# AnalogOutput.net
KiCad netlist of a schematic drawn in Altium Designer
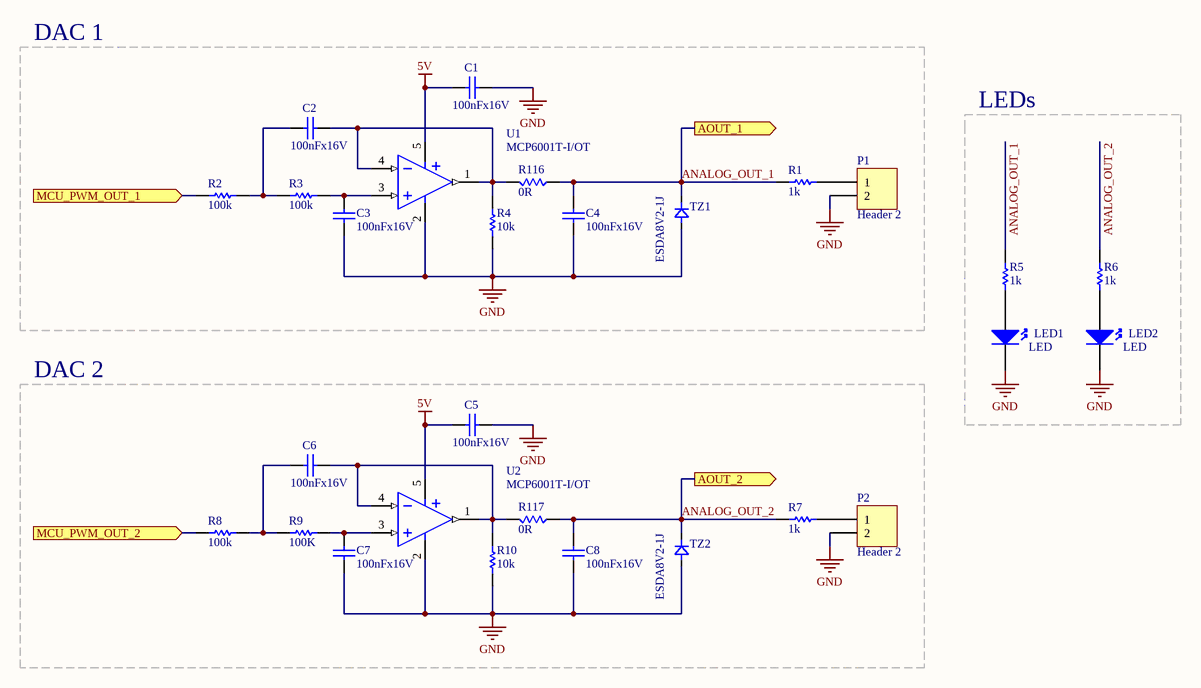
[diagram p0: AnalogOutput.SchDoc]

(export (version "E")
  (design (tool "Eeschema 10.0.6"))
  (components
    (comp (ref "C1")
      (value "100nFx16V")
      (footprint "DISC-0805")
      (description "Capacitor")
      (libsource (lib "IntLib") (part "Cap"))
    )
    (comp (ref "C2")
      (value "100nFx16V")
      (footprint "DISC-0805")
      (description "Capacitor")
      (libsource (lib "IntLib") (part "Cap"))
    )
    (comp (ref "C3")
      (value "100nFx16V")
      (footprint "DISC-0805")
      (description "Capacitor")
      (libsource (lib "IntLib") (part "Cap"))
    )
    (comp (ref "C4")
      (value "100nFx16V")
      (footprint "DISC-0805")
      (description "Capacitor")
      (libsource (lib "IntLib") (part "Cap"))
    )
    (comp (ref "C5")
      (value "100nFx16V")
      (footprint "DISC-0805")
      (description "Capacitor")
      (libsource (lib "IntLib") (part "Cap"))
    )
    (comp (ref "C6")
      (value "100nFx16V")
      (footprint "DISC-0805")
      (description "Capacitor")
      (libsource (lib "IntLib") (part "Cap"))
    )
    (comp (ref "C7")
      (value "100nFx16V")
      (footprint "DISC-0805")
      (description "Capacitor")
      (libsource (lib "IntLib") (part "Cap"))
    )
    (comp (ref "C8")
      (value "100nFx16V")
      (footprint "DISC-0805")
      (description "Capacitor")
      (libsource (lib "IntLib") (part "Cap"))
    )
    (comp (ref "LED1") (value "LED") (footprint "DISC-LED-0.1-PTH") (libsource (lib "IntLib") (part "LED")))
    (comp (ref "LED2") (value "LED") (footprint "DISC-LED-0.1-PTH") (libsource (lib "IntLib") (part "LED")))
    (comp (ref "P1")
      (value "Header 2")
      (footprint "CON-FLEXWIRE-0.5MM2-1X2")
      (description "Header, 2-Pin")
      (fields (field (name "PUBLISHER") "Altium Limited"))
      (libsource (lib "IntLib") (part "Header 2"))
    )
    (comp (ref "P2")
      (value "Header 2")
      (footprint "CON-FLEXWIRE-0.5MM2-1X2")
      (description "Header, 2-Pin")
      (fields (field (name "PUBLISHER") "Altium Limited"))
      (libsource (lib "IntLib") (part "Header 2"))
    )
    (comp (ref "R1")
      (value "1k")
      (footprint "DISC-0805")
      (description "Resistor")
      (libsource (lib "IntLib") (part "Res"))
    )
    (comp (ref "R2")
      (value "100k")
      (footprint "DISC-0805")
      (description "Resistor")
      (libsource (lib "IntLib") (part "Res"))
    )
    (comp (ref "R3")
      (value "100k")
      (footprint "DISC-0805")
      (description "Resistor")
      (libsource (lib "IntLib") (part "Res"))
    )
    (comp (ref "R4")
      (value "10k")
      (footprint "DISC-0805")
      (description "Resistor")
      (libsource (lib "IntLib") (part "Res"))
    )
    (comp (ref "R5")
      (value "1k")
      (footprint "DISC-0805")
      (description "Resistor")
      (libsource (lib "IntLib") (part "Res"))
    )
    (comp (ref "R6")
      (value "1k")
      (footprint "DISC-0805")
      (description "Resistor")
      (libsource (lib "IntLib") (part "Res"))
    )
    (comp (ref "R7")
      (value "1k")
      (footprint "DISC-0805")
      (description "Resistor")
      (libsource (lib "IntLib") (part "Res"))
    )
    (comp (ref "R8")
      (value "100k")
      (footprint "DISC-0805")
      (description "Resistor")
      (libsource (lib "IntLib") (part "Res"))
    )
    (comp (ref "R9")
      (value "100K")
      (footprint "DISC-0805")
      (description "Resistor")
      (libsource (lib "IntLib") (part "Res"))
    )
    (comp (ref "R10")
      (value "10k")
      (footprint "DISC-0805")
      (description "Resistor")
      (libsource (lib "IntLib") (part "Res"))
    )
    (comp (ref "R116")
      (value "0R")
      (footprint "DISC-0805")
      (description "Resistor")
      (libsource (lib "AUTOTRAC") (part "RESISTOR"))
    )
    (comp (ref "R117")
      (value "0R")
      (footprint "DISC-0805")
      (description "Resistor")
      (libsource (lib "AUTOTRAC") (part "RESISTOR"))
    )
    (comp (ref "TZ1")
      (value "ESDA8V2-1J")
      (footprint "DISC-SOD-323")
      (description "TVZ-Unidirectional")
      (libsource (lib "IntLib") (part "TVZ-Unidirectional"))
    )
    (comp (ref "TZ2")
      (value "ESDA8V2-1J")
      (footprint "DISC-SOD-323")
      (description "TVZ-Unidirectional")
      (libsource (lib "IntLib") (part "TVZ-Unidirectional"))
    )
    (comp (ref "U1")
      (value "MCP6001T-I/OT")
      (footprint "CI-SOT-23-5")
      (description "Operational Amplifiers - Op Amps Single 1.8V 1MHz")
      (libsource (lib "IntLib") (part "MCP6001T-I/OT"))
    )
    (comp (ref "U2")
      (value "MCP6001T-I/OT")
      (footprint "CI-SOT-23-5")
      (description "Operational Amplifiers - Op Amps Single 1.8V 1MHz")
      (libsource (lib "IntLib") (part "MCP6001T-I/OT"))
    )
  )
  (nets
    (net (code "1") (name "/ANALOG_OUT_1") (class "Default")
      (node (ref "C4") (pin "1") (pinfunction "1_1") (pintype "passive"))
      (node (ref "R1") (pin "2") (pinfunction "2_2") (pintype "passive"))
      (node (ref "R116") (pin "1") (pintype "passive"))
      (node (ref "R5") (pin "2") (pinfunction "2_2") (pintype "passive"))
      (node (ref "TZ1") (pin "2") (pinfunction "C_2") (pintype "passive"))
    )
    (net (code "2") (name "/ANALOG_OUT_2") (class "Default")
      (node (ref "C8") (pin "1") (pinfunction "1_1") (pintype "passive"))
      (node (ref "R117") (pin "1") (pintype "passive"))
      (node (ref "R6") (pin "2") (pinfunction "2_2") (pintype "passive"))
      (node (ref "R7") (pin "2") (pinfunction "2_2") (pintype "passive"))
      (node (ref "TZ2") (pin "2") (pinfunction "C_2") (pintype "passive"))
    )
    (net (code "3") (name "/MCU_PWM_OUT_1") (class "Default")
      (node (ref "R2") (pin "2") (pinfunction "2_2") (pintype "passive"))
    )
    (net (code "4") (name "/MCU_PWM_OUT_2") (class "Default")
      (node (ref "R8") (pin "2") (pinfunction "2_2") (pintype "passive"))
    )
    (net (code "5") (name "5V") (class "Default")
      (node (ref "C1") (pin "2") (pinfunction "2_2") (pintype "passive"))
      (node (ref "C5") (pin "2") (pinfunction "2_2") (pintype "passive"))
      (node (ref "U1") (pin "5") (pinfunction "V+_5") (pintype "power_in"))
      (node (ref "U2") (pin "5") (pinfunction "V+_5") (pintype "power_in"))
    )
    (net (code "6") (name "GND") (class "Default")
      (node (ref "C1") (pin "1") (pinfunction "1_1") (pintype "passive"))
      (node (ref "C3") (pin "2") (pinfunction "2_2") (pintype "passive"))
      (node (ref "C4") (pin "2") (pinfunction "2_2") (pintype "passive"))
      (node (ref "C5") (pin "1") (pinfunction "1_1") (pintype "passive"))
      (node (ref "C7") (pin "2") (pinfunction "2_2") (pintype "passive"))
      (node (ref "C8") (pin "2") (pinfunction "2_2") (pintype "passive"))
      (node (ref "LED1") (pin "2") (pinfunction "K_2") (pintype "passive"))
      (node (ref "LED2") (pin "2") (pinfunction "K_2") (pintype "passive"))
      (node (ref "P1") (pin "2") (pinfunction "2_2") (pintype "passive"))
      (node (ref "P2") (pin "2") (pinfunction "2_2") (pintype "passive"))
      (node (ref "R10") (pin "2") (pinfunction "2_2") (pintype "passive"))
      (node (ref "R4") (pin "2") (pinfunction "2_2") (pintype "passive"))
      (node (ref "TZ1") (pin "1") (pinfunction "A_1") (pintype "passive"))
      (node (ref "TZ2") (pin "1") (pinfunction "A_1") (pintype "passive"))
      (node (ref "U1") (pin "2") (pinfunction "V-_2") (pintype "power_in"))
      (node (ref "U2") (pin "2") (pinfunction "V-_2") (pintype "power_in"))
    )
    (net (code "7") (name "Net-(C2-Pad2)") (class "Default")
      (node (ref "C2") (pin "2") (pinfunction "2_2") (pintype "passive"))
      (node (ref "R2") (pin "1") (pinfunction "1_1") (pintype "passive"))
      (node (ref "R3") (pin "2") (pinfunction "2_2") (pintype "passive"))
    )
    (net (code "8") (name "Net-(C6-Pad2)") (class "Default")
      (node (ref "C6") (pin "2") (pinfunction "2_2") (pintype "passive"))
      (node (ref "R8") (pin "1") (pinfunction "1_1") (pintype "passive"))
      (node (ref "R9") (pin "2") (pinfunction "2_2") (pintype "passive"))
    )
    (net (code "9") (name "Net-(LED1-A)") (class "Default")
      (node (ref "LED1") (pin "1") (pinfunction "A_1") (pintype "passive"))
      (node (ref "R5") (pin "1") (pinfunction "1_1") (pintype "passive"))
    )
    (net (code "10") (name "Net-(LED2-A)") (class "Default")
      (node (ref "LED2") (pin "1") (pinfunction "A_1") (pintype "passive"))
      (node (ref "R6") (pin "1") (pinfunction "1_1") (pintype "passive"))
    )
    (net (code "11") (name "Net-(P1-Pad1)") (class "Default")
      (node (ref "P1") (pin "1") (pinfunction "1_1") (pintype "passive"))
      (node (ref "R1") (pin "1") (pinfunction "1_1") (pintype "passive"))
    )
    (net (code "12") (name "Net-(P2-Pad1)") (class "Default")
      (node (ref "P2") (pin "1") (pinfunction "1_1") (pintype "passive"))
      (node (ref "R7") (pin "1") (pinfunction "1_1") (pintype "passive"))
    )
    (net (code "13") (name "Net-(U1-IN+)") (class "Default")
      (node (ref "C3") (pin "1") (pinfunction "1_1") (pintype "passive"))
      (node (ref "R3") (pin "1") (pinfunction "1_1") (pintype "passive"))
      (node (ref "U1") (pin "3") (pinfunction "IN+_3") (pintype "input"))
    )
    (net (code "14") (name "Net-(U1-IN-)") (class "Default")
      (node (ref "C2") (pin "1") (pinfunction "1_1") (pintype "passive"))
      (node (ref "R116") (pin "2") (pintype "passive"))
      (node (ref "R4") (pin "1") (pinfunction "1_1") (pintype "passive"))
      (node (ref "U1") (pin "1") (pinfunction "Out_1") (pintype "output"))
      (node (ref "U1") (pin "4") (pinfunction "IN-_4") (pintype "input"))
    )
    (net (code "15") (name "Net-(U2-IN+)") (class "Default")
      (node (ref "C7") (pin "1") (pinfunction "1_1") (pintype "passive"))
      (node (ref "R9") (pin "1") (pinfunction "1_1") (pintype "passive"))
      (node (ref "U2") (pin "3") (pinfunction "IN+_3") (pintype "input"))
    )
    (net (code "16") (name "Net-(U2-IN-)") (class "Default")
      (node (ref "C6") (pin "1") (pinfunction "1_1") (pintype "passive"))
      (node (ref "R10") (pin "1") (pinfunction "1_1") (pintype "passive"))
      (node (ref "R117") (pin "2") (pintype "passive"))
      (node (ref "U2") (pin "1") (pinfunction "Out_1") (pintype "output"))
      (node (ref "U2") (pin "4") (pinfunction "IN-_4") (pintype "input"))
    )
  )
)
